# lighting.net
KiCad netlist of a schematic drawn in EAGLE
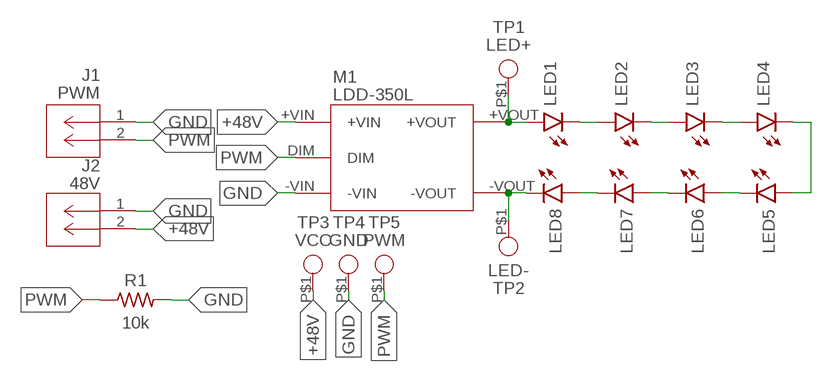
[diagram p0: schematic, sheet 1]

(export (version "E")
  (design (tool "Eeschema 10.0.6"))
  (components
    (comp (ref "J1")
      (value "PWM")
      (footprint "eagle-import:2PIN")
      (libsource (lib "eagle-import") (part "MICROLOCK-2PIN"))
    )
    (comp (ref "J2")
      (value "48V")
      (footprint "eagle-import:2PIN")
      (fields
        (field (name "MANUFACTURER_PART_NUMBER") "436500201")
        (field (name "COPYRIGHT") "Copyright (C) 2022 Ultra Librarian. All rights reserved.")
      )
      (libsource (lib "eagle-import") (part "2PINCON_436500201_MOL"))
    )
    (comp (ref "LED1")
      (value "XLAMP_XP-G3_ROYAL")
      (footprint "eagle-import:XLAMP_XP-G3")
      (libsource (lib "eagle-import") (part "XLAMP_XP-G3_ROYAL"))
    )
    (comp (ref "LED2")
      (value "XLAMP_XP-G3_ROYAL")
      (footprint "eagle-import:XLAMP_XP-G3")
      (libsource (lib "eagle-import") (part "XLAMP_XP-G3_ROYAL"))
    )
    (comp (ref "LED3")
      (value "XLAMP_XP-G3_ROYAL")
      (footprint "eagle-import:XLAMP_XP-G3")
      (libsource (lib "eagle-import") (part "XLAMP_XP-G3_ROYAL"))
    )
    (comp (ref "LED4")
      (value "XLAMP_XP-G3_ROYAL")
      (footprint "eagle-import:XLAMP_XP-G3")
      (libsource (lib "eagle-import") (part "XLAMP_XP-G3_ROYAL"))
    )
    (comp (ref "LED5")
      (value "XLAMP_XP-G3_ROYAL")
      (footprint "eagle-import:XLAMP_XP-G3")
      (libsource (lib "eagle-import") (part "XLAMP_XP-G3_ROYAL"))
    )
    (comp (ref "LED6")
      (value "XLAMP_XP-G3_ROYAL")
      (footprint "eagle-import:XLAMP_XP-G3")
      (libsource (lib "eagle-import") (part "XLAMP_XP-G3_ROYAL"))
    )
    (comp (ref "LED7")
      (value "XLAMP_XP-G3_ROYAL")
      (footprint "eagle-import:XLAMP_XP-G3")
      (libsource (lib "eagle-import") (part "XLAMP_XP-G3_ROYAL"))
    )
    (comp (ref "LED8")
      (value "XLAMP_XP-G3_ROYAL")
      (footprint "eagle-import:XLAMP_XP-G3")
      (libsource (lib "eagle-import") (part "XLAMP_XP-G3_ROYAL"))
    )
    (comp (ref "M1")
      (value "LDD-350L")
      (footprint "eagle-import:LDD-L")
      (libsource (lib "eagle-import") (part "LDD-350L"))
    )
    (comp (ref "R1")
      (value "10k")
      (footprint "eagle-import:RESC1608X60")
      (libsource (lib "eagle-import") (part "R-USCHIP-0603(1608-METRIC)_"))
    )
    (comp (ref "TP1")
      (value "LED+")
      (footprint "eagle-import:TP_CIRCLE_2.5MM")
      (libsource (lib "eagle-import") (part "TP_CIRCLE_2.5MM"))
    )
    (comp (ref "TP2")
      (value "LED-")
      (footprint "eagle-import:TP_CIRCLE_2.5MM")
      (libsource (lib "eagle-import") (part "TP_CIRCLE_2.5MM"))
    )
    (comp (ref "TP3")
      (value "VCC")
      (footprint "eagle-import:TP_CIRCLE_2.5MM")
      (libsource (lib "eagle-import") (part "TP_CIRCLE_2.5MM"))
    )
    (comp (ref "TP4")
      (value "GND")
      (footprint "eagle-import:TP_CIRCLE_2.5MM")
      (libsource (lib "eagle-import") (part "TP_CIRCLE_2.5MM"))
    )
    (comp (ref "TP5")
      (value "PWM")
      (footprint "eagle-import:TP_CIRCLE_2.5MM")
      (libsource (lib "eagle-import") (part "TP_CIRCLE_2.5MM"))
    )
  )
  (nets
    (net (code "1") (name "+48V") (class "Default")
      (node (ref "J2") (pin "2") (pinfunction "2_2") (pintype "passive"))
      (node (ref "M1") (pin "+VIN") (pinfunction "+VIN_+VIN") (pintype "bidirectional"))
      (node (ref "TP3") (pin "P$1") (pinfunction "P$1_P$1") (pintype "output"))
    )
    (net (code "2") (name "GND") (class "Default")
      (node (ref "J1") (pin "1") (pinfunction "2_1") (pintype "passive"))
      (node (ref "J2") (pin "1") (pinfunction "1_1") (pintype "passive"))
      (node (ref "M1") (pin "-VIN") (pinfunction "-VIN_-VIN") (pintype "bidirectional"))
      (node (ref "R1") (pin "2") (pinfunction "2_2") (pintype "passive"))
      (node (ref "TP4") (pin "P$1") (pinfunction "P$1_P$1") (pintype "output"))
    )
    (net (code "3") (name "Net-(LED1-A)") (class "Default")
      (node (ref "LED1") (pin "P$1") (pinfunction "A_P$1") (pintype "passive"))
      (node (ref "M1") (pin "+VOUT") (pinfunction "+VOUT_+VOUT") (pintype "bidirectional"))
      (node (ref "TP1") (pin "P$1") (pinfunction "P$1_P$1") (pintype "output"))
    )
    (net (code "4") (name "Net-(LED1-C)") (class "Default")
      (node (ref "LED1") (pin "P$2") (pinfunction "C_P$2") (pintype "passive"))
      (node (ref "LED2") (pin "P$1") (pinfunction "A_P$1") (pintype "passive"))
    )
    (net (code "5") (name "Net-(LED2-C)") (class "Default")
      (node (ref "LED2") (pin "P$2") (pinfunction "C_P$2") (pintype "passive"))
      (node (ref "LED3") (pin "P$1") (pinfunction "A_P$1") (pintype "passive"))
    )
    (net (code "6") (name "Net-(LED3-C)") (class "Default")
      (node (ref "LED3") (pin "P$2") (pinfunction "C_P$2") (pintype "passive"))
      (node (ref "LED4") (pin "P$1") (pinfunction "A_P$1") (pintype "passive"))
    )
    (net (code "7") (name "Net-(LED4-C)") (class "Default")
      (node (ref "LED4") (pin "P$2") (pinfunction "C_P$2") (pintype "passive"))
      (node (ref "LED5") (pin "P$1") (pinfunction "A_P$1") (pintype "passive"))
    )
    (net (code "8") (name "Net-(LED5-C)") (class "Default")
      (node (ref "LED5") (pin "P$2") (pinfunction "C_P$2") (pintype "passive"))
      (node (ref "LED6") (pin "P$1") (pinfunction "A_P$1") (pintype "passive"))
    )
    (net (code "9") (name "Net-(LED6-C)") (class "Default")
      (node (ref "LED6") (pin "P$2") (pinfunction "C_P$2") (pintype "passive"))
      (node (ref "LED7") (pin "P$1") (pinfunction "A_P$1") (pintype "passive"))
    )
    (net (code "10") (name "Net-(LED7-C)") (class "Default")
      (node (ref "LED7") (pin "P$2") (pinfunction "C_P$2") (pintype "passive"))
      (node (ref "LED8") (pin "P$1") (pinfunction "A_P$1") (pintype "passive"))
    )
    (net (code "11") (name "Net-(LED8-C)") (class "Default")
      (node (ref "LED8") (pin "P$2") (pinfunction "C_P$2") (pintype "passive"))
      (node (ref "M1") (pin "-VOUT") (pinfunction "-VOUT_-VOUT") (pintype "bidirectional"))
      (node (ref "TP2") (pin "P$1") (pinfunction "P$1_P$1") (pintype "output"))
    )
    (net (code "12") (name "PWM") (class "Default")
      (node (ref "J1") (pin "2") (pinfunction "3_2") (pintype "passive"))
      (node (ref "M1") (pin "DIM") (pinfunction "DIM_DIM") (pintype "bidirectional"))
      (node (ref "R1") (pin "1") (pinfunction "1_1") (pintype "passive"))
      (node (ref "TP5") (pin "P$1") (pinfunction "P$1_P$1") (pintype "output"))
    )
  )
)
